# stopwatch.net
KiCad netlist of a schematic drawn in EAGLE
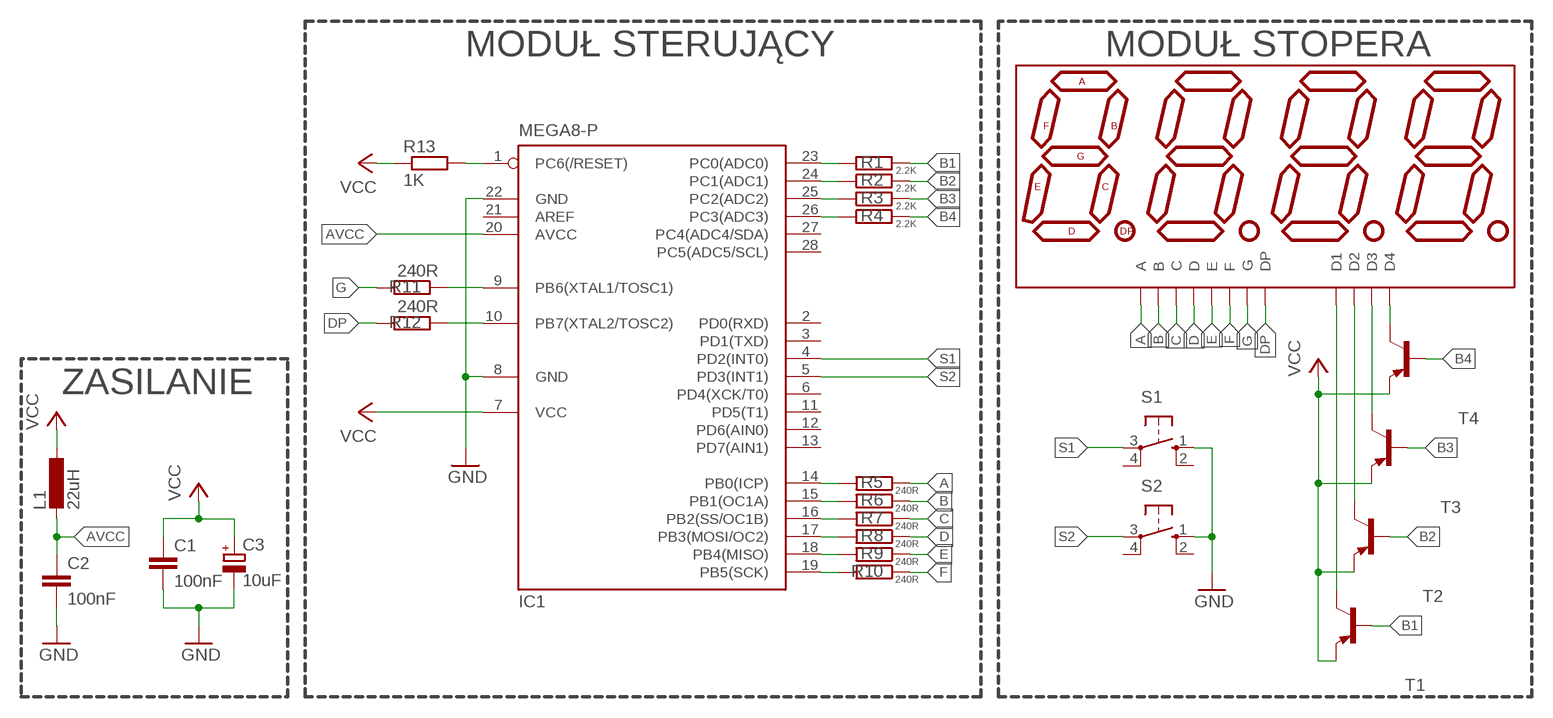
[diagram p0: schematic, sheet 1]

(export (version "E")
  (design (tool "Eeschema 10.0.6"))
  (components
    (comp (ref "C1")
      (value "100nF")
      (footprint "eagle-import:C050-025X075")
      (libsource (lib "eagle-import") (part "C-EU050-025X075"))
    )
    (comp (ref "C2")
      (value "100nF")
      (footprint "eagle-import:C050-025X075")
      (libsource (lib "eagle-import") (part "C-EU050-025X075"))
    )
    (comp (ref "C3")
      (value "10uF")
      (footprint "eagle-import:E2,5-6E")
      (libsource (lib "eagle-import") (part "CPOL-EUE2,5-6E"))
    )
    (comp (ref "DISP1")
      (value "ATA8041ARBJ")
      (footprint "eagle-import:7-SEGMENT-4DIGIT-20MM")
      (libsource (lib "eagle-import") (part "7-SEGMENT-4DIGIT-20MM-RED"))
    )
    (comp (ref "IC1")
      (value "MEGA8-P")
      (footprint "eagle-import:DIL28-3")
      (libsource (lib "eagle-import") (part "MEGA8-P"))
    )
    (comp (ref "L1")
      (value "22uH")
      (footprint "eagle-import:0204_7")
      (libsource (lib "eagle-import") (part "L-EU0204/7"))
    )
    (comp (ref "R1")
      (value "2.2K")
      (footprint "eagle-import:0204_7")
      (libsource (lib "eagle-import") (part "R-EU_0204/7"))
    )
    (comp (ref "R2")
      (value "2.2K")
      (footprint "eagle-import:0204_7")
      (libsource (lib "eagle-import") (part "R-EU_0204/7"))
    )
    (comp (ref "R3")
      (value "2.2K")
      (footprint "eagle-import:0204_7")
      (libsource (lib "eagle-import") (part "R-EU_0204/7"))
    )
    (comp (ref "R4")
      (value "2.2K")
      (footprint "eagle-import:0204_7")
      (libsource (lib "eagle-import") (part "R-EU_0204/7"))
    )
    (comp (ref "R5")
      (value "240R")
      (footprint "eagle-import:0204_7")
      (libsource (lib "eagle-import") (part "R-EU_0204/7"))
    )
    (comp (ref "R6")
      (value "240R")
      (footprint "eagle-import:0204_7")
      (libsource (lib "eagle-import") (part "R-EU_0204/7"))
    )
    (comp (ref "R7")
      (value "240R")
      (footprint "eagle-import:0204_7")
      (libsource (lib "eagle-import") (part "R-EU_0204/7"))
    )
    (comp (ref "R8")
      (value "240R")
      (footprint "eagle-import:0204_7")
      (libsource (lib "eagle-import") (part "R-EU_0204/7"))
    )
    (comp (ref "R9")
      (value "240R")
      (footprint "eagle-import:0204_7")
      (libsource (lib "eagle-import") (part "R-EU_0204/7"))
    )
    (comp (ref "R10")
      (value "240R")
      (footprint "eagle-import:0204_7")
      (libsource (lib "eagle-import") (part "R-EU_0204/7"))
    )
    (comp (ref "R11")
      (value "240R")
      (footprint "eagle-import:0204_7")
      (libsource (lib "eagle-import") (part "R-EU_0204/7"))
    )
    (comp (ref "R12")
      (value "240R")
      (footprint "eagle-import:0204_7")
      (libsource (lib "eagle-import") (part "R-EU_0204/7"))
    )
    (comp (ref "R13")
      (value "1K")
      (footprint "eagle-import:0204_7")
      (libsource (lib "eagle-import") (part "R-EU_0204/7"))
    )
    (comp (ref "S1")
      (value "10-XX")
      (footprint "eagle-import:B3F-10XX")
      (fields (field (name "MPN") "B3F-1000"))
      (libsource (lib "eagle-import") (part "10-XX"))
    )
    (comp (ref "S2")
      (value "10-XX")
      (footprint "eagle-import:B3F-10XX")
      (fields (field (name "MPN") "B3F-1000"))
      (libsource (lib "eagle-import") (part "10-XX"))
    )
    (comp (ref "T1")
      (value "BC557A-PNP-TO92-EBC")
      (footprint "eagle-import:TO92-EBC")
      (libsource (lib "eagle-import") (part "-PNP-TO92-EBCBC557A"))
    )
    (comp (ref "T2")
      (value "BC557A-PNP-TO92-EBC")
      (footprint "eagle-import:TO92-EBC")
      (libsource (lib "eagle-import") (part "-PNP-TO92-EBCBC557A"))
    )
    (comp (ref "T3")
      (value "BC557A-PNP-TO92-EBC")
      (footprint "eagle-import:TO92-EBC")
      (libsource (lib "eagle-import") (part "-PNP-TO92-EBCBC557A"))
    )
    (comp (ref "T4")
      (value "BC557A-PNP-TO92-EBC")
      (footprint "eagle-import:TO92-EBC")
      (libsource (lib "eagle-import") (part "-PNP-TO92-EBCBC557A"))
    )
  )
  (nets
    (net (code "1") (name "A") (class "Default")
      (node (ref "DISP1") (pin "11") (pinfunction "A_11") (pintype "bidirectional"))
      (node (ref "R5") (pin "1") (pinfunction "1_1") (pintype "passive"))
    )
    (net (code "2") (name "AVCC") (class "Default")
      (node (ref "C2") (pin "1") (pinfunction "1_1") (pintype "passive"))
      (node (ref "IC1") (pin "20") (pinfunction "AVCC_20") (pintype "power_in"))
      (node (ref "L1") (pin "2") (pinfunction "2_2") (pintype "passive"))
    )
    (net (code "3") (name "B") (class "Default")
      (node (ref "DISP1") (pin "7") (pinfunction "B_7") (pintype "bidirectional"))
      (node (ref "R6") (pin "1") (pinfunction "1_1") (pintype "passive"))
    )
    (net (code "4") (name "B1") (class "Default")
      (node (ref "R1") (pin "2") (pinfunction "2_2") (pintype "passive"))
      (node (ref "T1") (pin "B") (pinfunction "B_B") (pintype "passive"))
    )
    (net (code "5") (name "B2") (class "Default")
      (node (ref "R2") (pin "2") (pinfunction "2_2") (pintype "passive"))
      (node (ref "T2") (pin "B") (pinfunction "B_B") (pintype "passive"))
    )
    (net (code "6") (name "B3") (class "Default")
      (node (ref "R3") (pin "2") (pinfunction "2_2") (pintype "passive"))
      (node (ref "T3") (pin "B") (pinfunction "B_B") (pintype "passive"))
    )
    (net (code "7") (name "B4") (class "Default")
      (node (ref "R4") (pin "2") (pinfunction "2_2") (pintype "passive"))
      (node (ref "T4") (pin "B") (pinfunction "B_B") (pintype "passive"))
    )
    (net (code "8") (name "C") (class "Default")
      (node (ref "DISP1") (pin "4") (pinfunction "C_4") (pintype "bidirectional"))
      (node (ref "R7") (pin "1") (pinfunction "1_1") (pintype "passive"))
    )
    (net (code "9") (name "D") (class "Default")
      (node (ref "DISP1") (pin "2") (pinfunction "D_2") (pintype "bidirectional"))
      (node (ref "R8") (pin "1") (pinfunction "1_1") (pintype "passive"))
    )
    (net (code "10") (name "DP") (class "Default")
      (node (ref "DISP1") (pin "3") (pinfunction "DP_3") (pintype "bidirectional"))
      (node (ref "R12") (pin "2") (pinfunction "2_2") (pintype "passive"))
    )
    (net (code "11") (name "E") (class "Default")
      (node (ref "DISP1") (pin "1") (pinfunction "E_1") (pintype "bidirectional"))
      (node (ref "R9") (pin "1") (pinfunction "1_1") (pintype "passive"))
    )
    (net (code "12") (name "F") (class "Default")
      (node (ref "DISP1") (pin "10") (pinfunction "F_10") (pintype "bidirectional"))
      (node (ref "R10") (pin "1") (pinfunction "1_1") (pintype "passive"))
    )
    (net (code "13") (name "G") (class "Default")
      (node (ref "DISP1") (pin "5") (pinfunction "G_5") (pintype "bidirectional"))
      (node (ref "R11") (pin "2") (pinfunction "2_2") (pintype "passive"))
    )
    (net (code "14") (name "GND") (class "Default")
      (node (ref "C1") (pin "2") (pinfunction "2_2") (pintype "passive"))
      (node (ref "C2") (pin "2") (pinfunction "2_2") (pintype "passive"))
      (node (ref "C3") (pin "-") (pinfunction "-_-") (pintype "passive"))
      (node (ref "IC1") (pin "22") (pinfunction "GND_22") (pintype "power_in"))
      (node (ref "IC1") (pin "8") (pinfunction "GND_8") (pintype "power_in"))
      (node (ref "S1") (pin "1") (pinfunction "S_1") (pintype "passive"))
      (node (ref "S2") (pin "1") (pinfunction "S_1") (pintype "passive"))
    )
    (net (code "15") (name "Net-(DISP1-D1)") (class "Default")
      (node (ref "DISP1") (pin "12") (pinfunction "D1_12") (pintype "bidirectional"))
      (node (ref "T1") (pin "C") (pinfunction "C_C") (pintype "passive"))
    )
    (net (code "16") (name "Net-(DISP1-D2)") (class "Default")
      (node (ref "DISP1") (pin "9") (pinfunction "D2_9") (pintype "bidirectional"))
      (node (ref "T2") (pin "C") (pinfunction "C_C") (pintype "passive"))
    )
    (net (code "17") (name "Net-(DISP1-D3)") (class "Default")
      (node (ref "DISP1") (pin "8") (pinfunction "D3_8") (pintype "bidirectional"))
      (node (ref "T3") (pin "C") (pinfunction "C_C") (pintype "passive"))
    )
    (net (code "18") (name "Net-(DISP1-D4)") (class "Default")
      (node (ref "DISP1") (pin "6") (pinfunction "D4_6") (pintype "bidirectional"))
      (node (ref "T4") (pin "C") (pinfunction "C_C") (pintype "passive"))
    )
    (net (code "19") (name "Net-(IC1-PB0(ICP))") (class "Default")
      (node (ref "IC1") (pin "14") (pinfunction "PB0(ICP)_14") (pintype "bidirectional"))
      (node (ref "R5") (pin "2") (pinfunction "2_2") (pintype "passive"))
    )
    (net (code "20") (name "Net-(IC1-PB1(OC1A))") (class "Default")
      (node (ref "IC1") (pin "15") (pinfunction "PB1(OC1A)_15") (pintype "bidirectional"))
      (node (ref "R6") (pin "2") (pinfunction "2_2") (pintype "passive"))
    )
    (net (code "21") (name "Net-(IC1-PB2(SS{slash}OC1B))") (class "Default")
      (node (ref "IC1") (pin "16") (pinfunction "PB2(SS/OC1B)_16") (pintype "bidirectional"))
      (node (ref "R7") (pin "2") (pinfunction "2_2") (pintype "passive"))
    )
    (net (code "22") (name "Net-(IC1-PB3(MOSI{slash}OC2))") (class "Default")
      (node (ref "IC1") (pin "17") (pinfunction "PB3(MOSI/OC2)_17") (pintype "bidirectional"))
      (node (ref "R8") (pin "2") (pinfunction "2_2") (pintype "passive"))
    )
    (net (code "23") (name "Net-(IC1-PB4(MISO))") (class "Default")
      (node (ref "IC1") (pin "18") (pinfunction "PB4(MISO)_18") (pintype "bidirectional"))
      (node (ref "R9") (pin "2") (pinfunction "2_2") (pintype "passive"))
    )
    (net (code "24") (name "Net-(IC1-PB5(SCK))") (class "Default")
      (node (ref "IC1") (pin "19") (pinfunction "PB5(SCK)_19") (pintype "bidirectional"))
      (node (ref "R10") (pin "2") (pinfunction "2_2") (pintype "passive"))
    )
    (net (code "25") (name "Net-(IC1-PB6(XTAL1{slash}TOSC1))") (class "Default")
      (node (ref "IC1") (pin "9") (pinfunction "PB6(XTAL1/TOSC1)_9") (pintype "bidirectional"))
      (node (ref "R11") (pin "1") (pinfunction "1_1") (pintype "passive"))
    )
    (net (code "26") (name "Net-(IC1-PB7(XTAL2{slash}TOSC2))") (class "Default")
      (node (ref "IC1") (pin "10") (pinfunction "PB7(XTAL2/TOSC2)_10") (pintype "bidirectional"))
      (node (ref "R12") (pin "1") (pinfunction "1_1") (pintype "passive"))
    )
    (net (code "27") (name "Net-(IC1-PC0(ADC0))") (class "Default")
      (node (ref "IC1") (pin "23") (pinfunction "PC0(ADC0)_23") (pintype "bidirectional"))
      (node (ref "R1") (pin "1") (pinfunction "1_1") (pintype "passive"))
    )
    (net (code "28") (name "Net-(IC1-PC1(ADC1))") (class "Default")
      (node (ref "IC1") (pin "24") (pinfunction "PC1(ADC1)_24") (pintype "bidirectional"))
      (node (ref "R2") (pin "1") (pinfunction "1_1") (pintype "passive"))
    )
    (net (code "29") (name "Net-(IC1-PC2(ADC2))") (class "Default")
      (node (ref "IC1") (pin "25") (pinfunction "PC2(ADC2)_25") (pintype "bidirectional"))
      (node (ref "R3") (pin "1") (pinfunction "1_1") (pintype "passive"))
    )
    (net (code "30") (name "Net-(IC1-PC3(ADC3))") (class "Default")
      (node (ref "IC1") (pin "26") (pinfunction "PC3(ADC3)_26") (pintype "bidirectional"))
      (node (ref "R4") (pin "1") (pinfunction "1_1") (pintype "passive"))
    )
    (net (code "31") (name "Net-(IC1-PC6({slash}RESET))") (class "Default")
      (node (ref "IC1") (pin "1") (pinfunction "PC6(/RESET)_1") (pintype "bidirectional"))
      (node (ref "R13") (pin "2") (pinfunction "2_2") (pintype "passive"))
    )
    (net (code "32") (name "S1") (class "Default")
      (node (ref "IC1") (pin "4") (pinfunction "PD2(INT0)_4") (pintype "bidirectional"))
      (node (ref "S1") (pin "3") (pinfunction "P_3") (pintype "passive"))
    )
    (net (code "33") (name "S2") (class "Default")
      (node (ref "IC1") (pin "5") (pinfunction "PD3(INT1)_5") (pintype "bidirectional"))
      (node (ref "S2") (pin "3") (pinfunction "P_3") (pintype "passive"))
    )
    (net (code "34") (name "VCC") (class "Default")
      (node (ref "C1") (pin "1") (pinfunction "1_1") (pintype "passive"))
      (node (ref "C3") (pin "+") (pinfunction "+_+") (pintype "passive"))
      (node (ref "IC1") (pin "7") (pinfunction "VCC_7") (pintype "power_in"))
      (node (ref "L1") (pin "1") (pinfunction "1_1") (pintype "passive"))
      (node (ref "R13") (pin "1") (pinfunction "1_1") (pintype "passive"))
      (node (ref "T1") (pin "E") (pinfunction "E_E") (pintype "passive"))
      (node (ref "T2") (pin "E") (pinfunction "E_E") (pintype "passive"))
      (node (ref "T3") (pin "E") (pinfunction "E_E") (pintype "passive"))
      (node (ref "T4") (pin "E") (pinfunction "E_E") (pintype "passive"))
    )
    (net (code "35") (name "unconnected-(IC1-AREF-Pad21)") (class "Default")
      (node (ref "IC1") (pin "21") (pinfunction "AREF_21") (pintype "passive"))
    )
    (net (code "36") (name "unconnected-(IC1-PC4(ADC4{slash}SDA)-Pad27)") (class "Default")
      (node (ref "IC1") (pin "27") (pinfunction "PC4(ADC4/SDA)_27") (pintype "bidirectional"))
    )
    (net (code "37") (name "unconnected-(IC1-PC5(ADC5{slash}SCL)-Pad28)") (class "Default")
      (node (ref "IC1") (pin "28") (pinfunction "PC5(ADC5/SCL)_28") (pintype "bidirectional"))
    )
    (net (code "38") (name "unconnected-(IC1-PD0(RXD)-Pad2)") (class "Default")
      (node (ref "IC1") (pin "2") (pinfunction "PD0(RXD)_2") (pintype "bidirectional"))
    )
    (net (code "39") (name "unconnected-(IC1-PD1(TXD)-Pad3)") (class "Default")
      (node (ref "IC1") (pin "3") (pinfunction "PD1(TXD)_3") (pintype "bidirectional"))
    )
    (net (code "40") (name "unconnected-(IC1-PD4(XCK{slash}T0)-Pad6)") (class "Default")
      (node (ref "IC1") (pin "6") (pinfunction "PD4(XCK/T0)_6") (pintype "bidirectional"))
    )
    (net (code "41") (name "unconnected-(IC1-PD5(T1)-Pad11)") (class "Default")
      (node (ref "IC1") (pin "11") (pinfunction "PD5(T1)_11") (pintype "bidirectional"))
    )
    (net (code "42") (name "unconnected-(IC1-PD6(AIN0)-Pad12)") (class "Default")
      (node (ref "IC1") (pin "12") (pinfunction "PD6(AIN0)_12") (pintype "bidirectional"))
    )
    (net (code "43") (name "unconnected-(IC1-PD7(AIN1)-Pad13)") (class "Default")
      (node (ref "IC1") (pin "13") (pinfunction "PD7(AIN1)_13") (pintype "bidirectional"))
    )
    (net (code "44") (name "unconnected-(S1-P1-Pad4)") (class "Default")
      (node (ref "S1") (pin "4") (pinfunction "P1_4") (pintype "passive"))
    )
    (net (code "45") (name "unconnected-(S1-S1-Pad2)") (class "Default")
      (node (ref "S1") (pin "2") (pinfunction "S1_2") (pintype "passive"))
    )
    (net (code "46") (name "unconnected-(S2-P1-Pad4)") (class "Default")
      (node (ref "S2") (pin "4") (pinfunction "P1_4") (pintype "passive"))
    )
    (net (code "47") (name "unconnected-(S2-S1-Pad2)") (class "Default")
      (node (ref "S2") (pin "2") (pinfunction "S1_2") (pintype "passive"))
    )
  )
)
